# sub.net
KiCad netlist of a schematic drawn in EAGLE
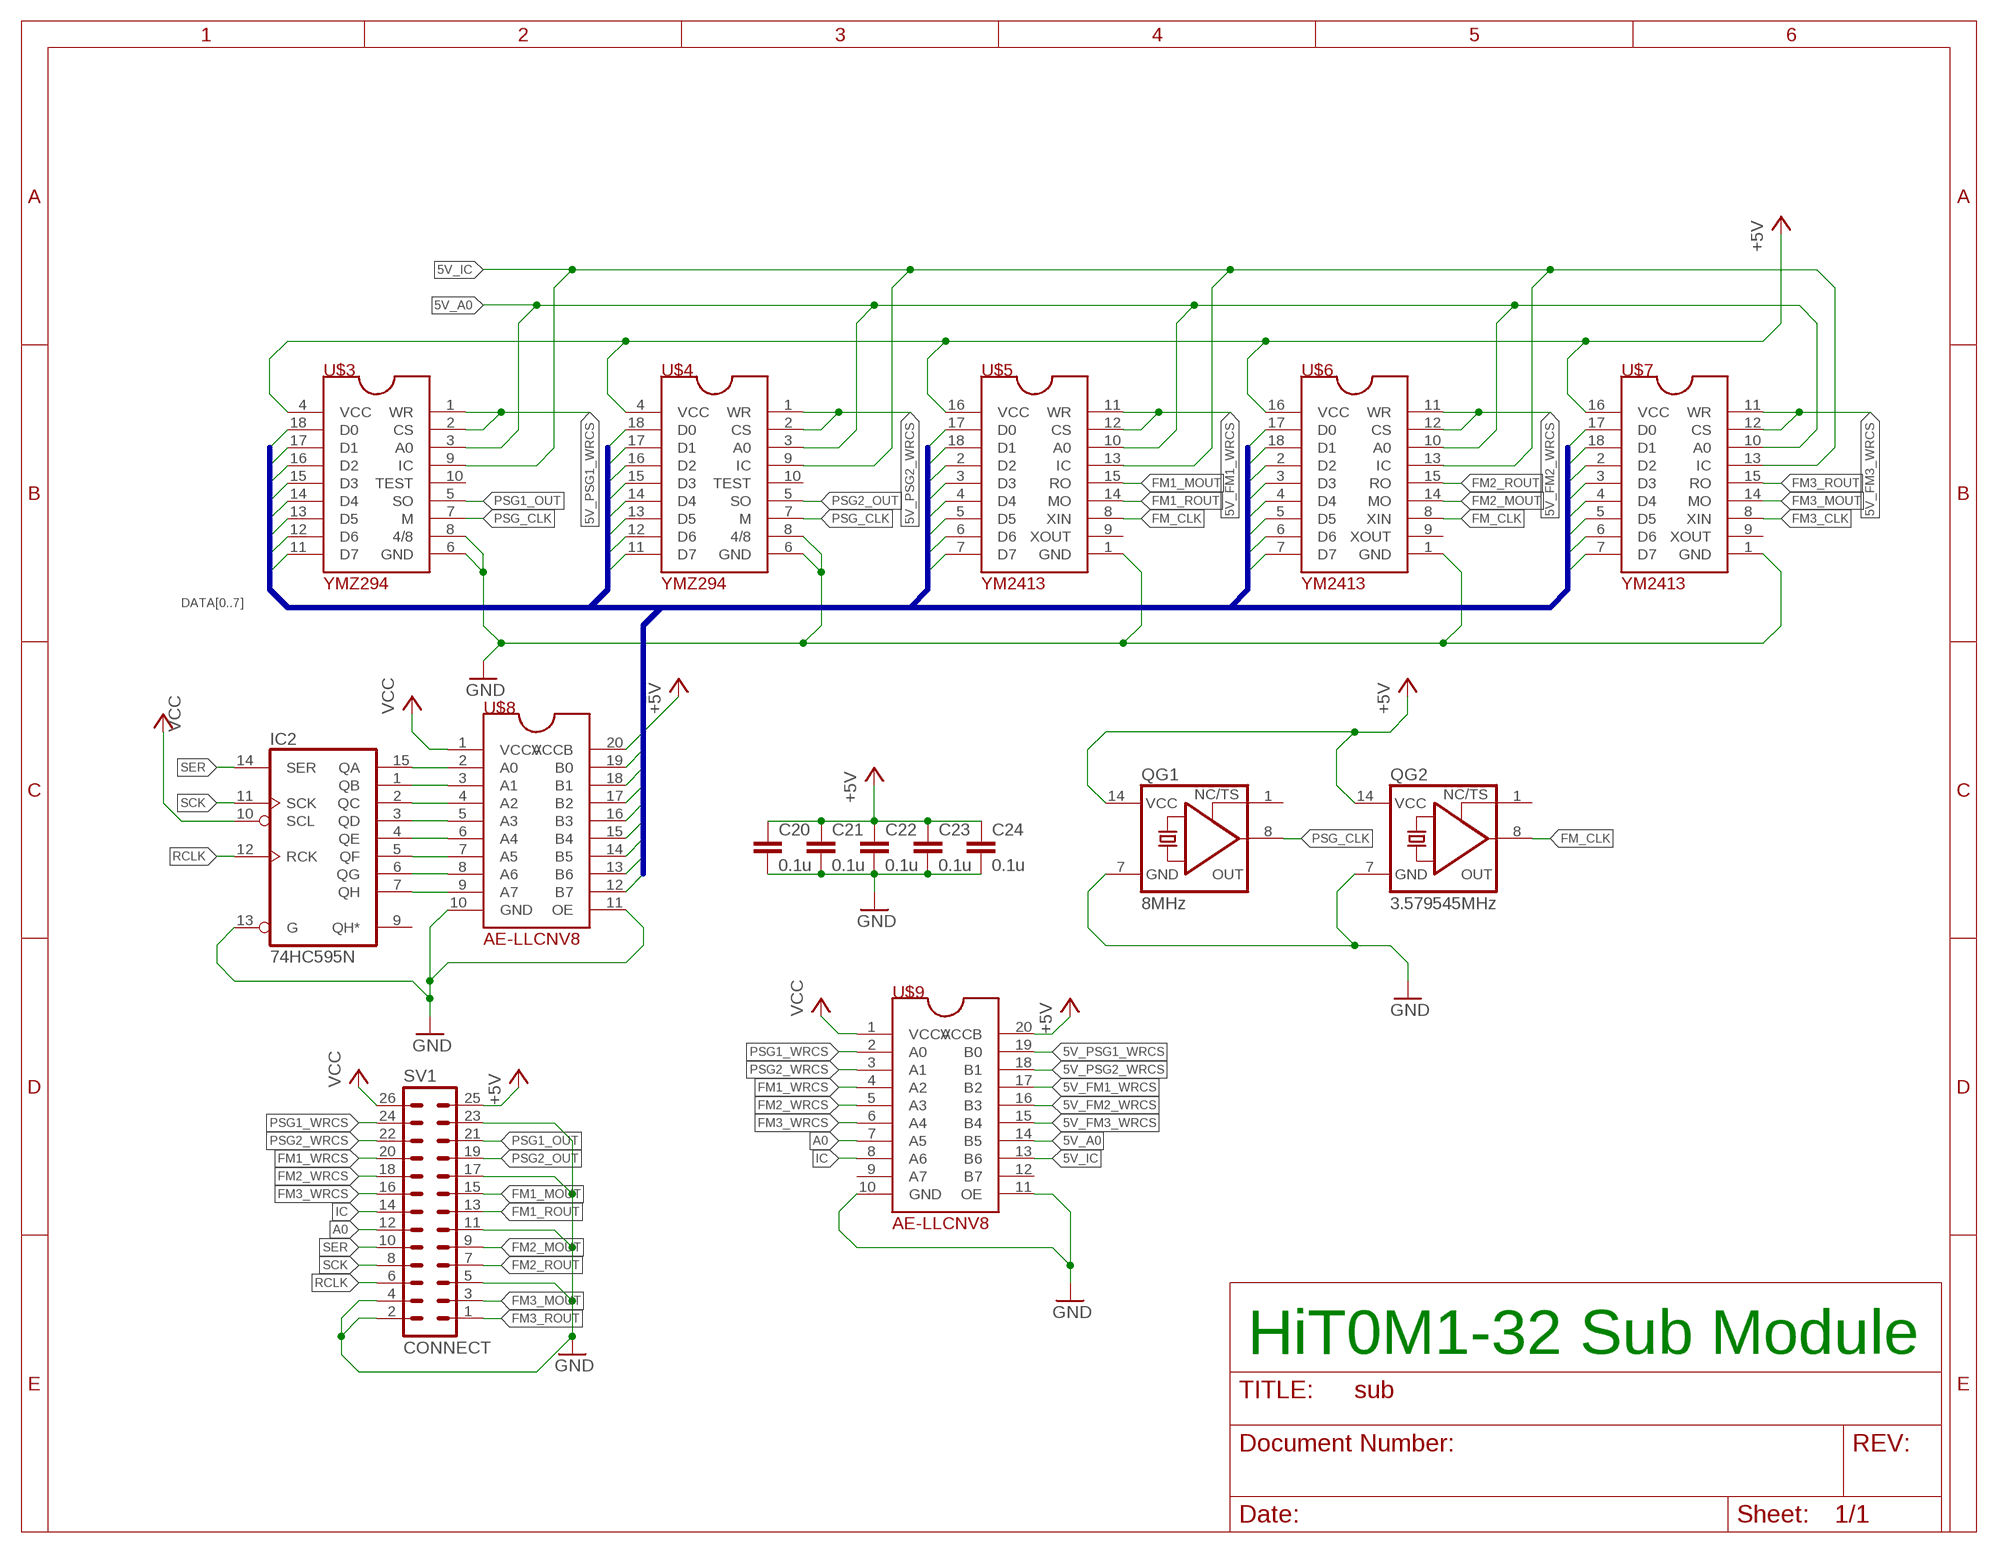
[diagram p0: schematic, sheet 1]

(export (version "E")
  (design (tool "Eeschema 10.0.6"))
  (components
    (comp (ref "C20")
      (value "0.1u")
      (footprint "eagle-import:C025-025X050")
      (libsource (lib "eagle-import") (part "C-EU025-025X050"))
    )
    (comp (ref "C21")
      (value "0.1u")
      (footprint "eagle-import:C025-025X050")
      (libsource (lib "eagle-import") (part "C-EU025-025X050"))
    )
    (comp (ref "C22")
      (value "0.1u")
      (footprint "eagle-import:C025-025X050")
      (libsource (lib "eagle-import") (part "C-EU025-025X050"))
    )
    (comp (ref "C23")
      (value "0.1u")
      (footprint "eagle-import:C025-025X050")
      (libsource (lib "eagle-import") (part "C-EU025-025X050"))
    )
    (comp (ref "C24")
      (value "0.1u")
      (footprint "eagle-import:C025-025X050")
      (libsource (lib "eagle-import") (part "C-EU025-025X050"))
    )
    (comp (ref "IC2")
      (value "74HC595N")
      (footprint "eagle-import:DIL16")
      (libsource (lib "eagle-import") (part "74595NHC"))
    )
    (comp (ref "QG1")
      (value "8MHz")
      (footprint "eagle-import:DIL14S")
      (libsource (lib "eagle-import") (part "XO-14"))
    )
    (comp (ref "QG2")
      (value "3.579545MHz")
      (footprint "eagle-import:DIL14S")
      (libsource (lib "eagle-import") (part "XO-14"))
    )
    (comp (ref "SV1")
      (value "CONNECT")
      (footprint "eagle-import:MA13-2")
      (libsource (lib "eagle-import") (part "MA13-2"))
    )
    (comp (ref "U$3")
      (value "YMZ294")
      (footprint "eagle-import:DIL18")
      (libsource (lib "eagle-import") (part "YMZ294YMZ294"))
    )
    (comp (ref "U$4")
      (value "YMZ294")
      (footprint "eagle-import:DIL18")
      (libsource (lib "eagle-import") (part "YMZ294YMZ294"))
    )
    (comp (ref "U$5")
      (value "YM2413")
      (footprint "eagle-import:DIL18")
      (libsource (lib "eagle-import") (part "YM2413"))
    )
    (comp (ref "U$6")
      (value "YM2413")
      (footprint "eagle-import:DIL18")
      (libsource (lib "eagle-import") (part "YM2413"))
    )
    (comp (ref "U$7")
      (value "YM2413")
      (footprint "eagle-import:DIL18")
      (libsource (lib "eagle-import") (part "YM2413"))
    )
    (comp (ref "U$8")
      (value "AE-LLCNV8")
      (footprint "eagle-import:DIL20")
      (libsource (lib "eagle-import") (part "AE-LLCNV8AE-LLCNV8"))
    )
    (comp (ref "U$9")
      (value "AE-LLCNV8")
      (footprint "eagle-import:DIL20")
      (libsource (lib "eagle-import") (part "AE-LLCNV8AE-LLCNV8"))
    )
  )
  (nets
    (net (code "1") (name "+5V") (class "Default")
      (node (ref "C20") (pin "1") (pinfunction "1_1") (pintype "passive"))
      (node (ref "C21") (pin "1") (pinfunction "1_1") (pintype "passive"))
      (node (ref "C22") (pin "1") (pinfunction "1_1") (pintype "passive"))
      (node (ref "C23") (pin "1") (pinfunction "1_1") (pintype "passive"))
      (node (ref "C24") (pin "1") (pinfunction "1_1") (pintype "passive"))
      (node (ref "QG1") (pin "14") (pinfunction "VCC_14") (pintype "power_in"))
      (node (ref "QG2") (pin "14") (pinfunction "VCC_14") (pintype "power_in"))
      (node (ref "SV1") (pin "25") (pinfunction "25_25") (pintype "passive"))
      (node (ref "U$3") (pin "4") (pinfunction "VCC_4") (pintype "bidirectional"))
      (node (ref "U$4") (pin "4") (pinfunction "VCC_4") (pintype "bidirectional"))
      (node (ref "U$5") (pin "16") (pinfunction "VCC_16") (pintype "bidirectional"))
      (node (ref "U$6") (pin "16") (pinfunction "VCC_16") (pintype "bidirectional"))
      (node (ref "U$7") (pin "16") (pinfunction "VCC_16") (pintype "bidirectional"))
      (node (ref "U$8") (pin "20") (pinfunction "VCCB_20") (pintype "bidirectional"))
      (node (ref "U$9") (pin "20") (pinfunction "VCCB_20") (pintype "bidirectional"))
    )
    (net (code "2") (name "/DATA0") (class "Default")
      (node (ref "U$3") (pin "18") (pinfunction "D0_18") (pintype "bidirectional"))
      (node (ref "U$4") (pin "18") (pinfunction "D0_18") (pintype "bidirectional"))
      (node (ref "U$5") (pin "17") (pinfunction "D0_17") (pintype "bidirectional"))
      (node (ref "U$6") (pin "17") (pinfunction "D0_17") (pintype "bidirectional"))
      (node (ref "U$7") (pin "17") (pinfunction "D0_17") (pintype "bidirectional"))
      (node (ref "U$8") (pin "19") (pinfunction "B0_19") (pintype "bidirectional"))
    )
    (net (code "3") (name "/DATA1") (class "Default")
      (node (ref "U$3") (pin "17") (pinfunction "D1_17") (pintype "bidirectional"))
      (node (ref "U$4") (pin "17") (pinfunction "D1_17") (pintype "bidirectional"))
      (node (ref "U$5") (pin "18") (pinfunction "D1_18") (pintype "bidirectional"))
      (node (ref "U$6") (pin "18") (pinfunction "D1_18") (pintype "bidirectional"))
      (node (ref "U$7") (pin "18") (pinfunction "D1_18") (pintype "bidirectional"))
      (node (ref "U$8") (pin "18") (pinfunction "B1_18") (pintype "bidirectional"))
    )
    (net (code "4") (name "/DATA2") (class "Default")
      (node (ref "U$3") (pin "16") (pinfunction "D2_16") (pintype "bidirectional"))
      (node (ref "U$4") (pin "16") (pinfunction "D2_16") (pintype "bidirectional"))
      (node (ref "U$5") (pin "2") (pinfunction "D2_2") (pintype "bidirectional"))
      (node (ref "U$6") (pin "2") (pinfunction "D2_2") (pintype "bidirectional"))
      (node (ref "U$7") (pin "2") (pinfunction "D2_2") (pintype "bidirectional"))
      (node (ref "U$8") (pin "17") (pinfunction "B2_17") (pintype "bidirectional"))
    )
    (net (code "5") (name "/DATA3") (class "Default")
      (node (ref "U$3") (pin "15") (pinfunction "D3_15") (pintype "bidirectional"))
      (node (ref "U$4") (pin "15") (pinfunction "D3_15") (pintype "bidirectional"))
      (node (ref "U$5") (pin "3") (pinfunction "D3_3") (pintype "bidirectional"))
      (node (ref "U$6") (pin "3") (pinfunction "D3_3") (pintype "bidirectional"))
      (node (ref "U$7") (pin "3") (pinfunction "D3_3") (pintype "bidirectional"))
      (node (ref "U$8") (pin "16") (pinfunction "B3_16") (pintype "bidirectional"))
    )
    (net (code "6") (name "/DATA4") (class "Default")
      (node (ref "U$3") (pin "14") (pinfunction "D4_14") (pintype "bidirectional"))
      (node (ref "U$4") (pin "14") (pinfunction "D4_14") (pintype "bidirectional"))
      (node (ref "U$5") (pin "4") (pinfunction "D4_4") (pintype "bidirectional"))
      (node (ref "U$6") (pin "4") (pinfunction "D4_4") (pintype "bidirectional"))
      (node (ref "U$7") (pin "4") (pinfunction "D4_4") (pintype "bidirectional"))
      (node (ref "U$8") (pin "15") (pinfunction "B4_15") (pintype "bidirectional"))
    )
    (net (code "7") (name "/DATA5") (class "Default")
      (node (ref "U$3") (pin "13") (pinfunction "D5_13") (pintype "bidirectional"))
      (node (ref "U$4") (pin "13") (pinfunction "D5_13") (pintype "bidirectional"))
      (node (ref "U$5") (pin "5") (pinfunction "D5_5") (pintype "bidirectional"))
      (node (ref "U$6") (pin "5") (pinfunction "D5_5") (pintype "bidirectional"))
      (node (ref "U$7") (pin "5") (pinfunction "D5_5") (pintype "bidirectional"))
      (node (ref "U$8") (pin "14") (pinfunction "B5_14") (pintype "bidirectional"))
    )
    (net (code "8") (name "/DATA6") (class "Default")
      (node (ref "U$3") (pin "12") (pinfunction "D6_12") (pintype "bidirectional"))
      (node (ref "U$4") (pin "12") (pinfunction "D6_12") (pintype "bidirectional"))
      (node (ref "U$5") (pin "6") (pinfunction "D6_6") (pintype "bidirectional"))
      (node (ref "U$6") (pin "6") (pinfunction "D6_6") (pintype "bidirectional"))
      (node (ref "U$7") (pin "6") (pinfunction "D6_6") (pintype "bidirectional"))
      (node (ref "U$8") (pin "13") (pinfunction "B6_13") (pintype "bidirectional"))
    )
    (net (code "9") (name "/DATA7") (class "Default")
      (node (ref "U$3") (pin "11") (pinfunction "D7_11") (pintype "bidirectional"))
      (node (ref "U$4") (pin "11") (pinfunction "D7_11") (pintype "bidirectional"))
      (node (ref "U$5") (pin "7") (pinfunction "D7_7") (pintype "bidirectional"))
      (node (ref "U$6") (pin "7") (pinfunction "D7_7") (pintype "bidirectional"))
      (node (ref "U$7") (pin "7") (pinfunction "D7_7") (pintype "bidirectional"))
      (node (ref "U$8") (pin "12") (pinfunction "B7_12") (pintype "bidirectional"))
    )
    (net (code "11") (name "5V_A0") (class "Default")
      (node (ref "U$3") (pin "3") (pinfunction "A0_3") (pintype "bidirectional"))
      (node (ref "U$4") (pin "3") (pinfunction "A0_3") (pintype "bidirectional"))
      (node (ref "U$5") (pin "10") (pinfunction "A0_10") (pintype "bidirectional"))
      (node (ref "U$6") (pin "10") (pinfunction "A0_10") (pintype "bidirectional"))
      (node (ref "U$7") (pin "10") (pinfunction "A0_10") (pintype "bidirectional"))
      (node (ref "U$9") (pin "14") (pinfunction "B5_14") (pintype "bidirectional"))
    )
    (net (code "12") (name "5V_FM1_WRCS") (class "Default")
      (node (ref "U$5") (pin "11") (pinfunction "WR_11") (pintype "bidirectional"))
      (node (ref "U$5") (pin "12") (pinfunction "CS_12") (pintype "bidirectional"))
      (node (ref "U$9") (pin "17") (pinfunction "B2_17") (pintype "bidirectional"))
    )
    (net (code "13") (name "5V_FM2_WRCS") (class "Default")
      (node (ref "U$6") (pin "11") (pinfunction "WR_11") (pintype "bidirectional"))
      (node (ref "U$6") (pin "12") (pinfunction "CS_12") (pintype "bidirectional"))
      (node (ref "U$9") (pin "16") (pinfunction "B3_16") (pintype "bidirectional"))
    )
    (net (code "14") (name "5V_FM3_WRCS") (class "Default")
      (node (ref "U$7") (pin "11") (pinfunction "WR_11") (pintype "bidirectional"))
      (node (ref "U$7") (pin "12") (pinfunction "CS_12") (pintype "bidirectional"))
      (node (ref "U$9") (pin "15") (pinfunction "B4_15") (pintype "bidirectional"))
    )
    (net (code "15") (name "5V_IC") (class "Default")
      (node (ref "U$3") (pin "9") (pinfunction "IC_9") (pintype "bidirectional"))
      (node (ref "U$4") (pin "9") (pinfunction "IC_9") (pintype "bidirectional"))
      (node (ref "U$5") (pin "13") (pinfunction "IC_13") (pintype "bidirectional"))
      (node (ref "U$6") (pin "13") (pinfunction "IC_13") (pintype "bidirectional"))
      (node (ref "U$7") (pin "13") (pinfunction "IC_13") (pintype "bidirectional"))
      (node (ref "U$9") (pin "13") (pinfunction "B6_13") (pintype "bidirectional"))
    )
    (net (code "16") (name "5V_PSG1_WRCS") (class "Default")
      (node (ref "U$3") (pin "1") (pinfunction "WR_1") (pintype "bidirectional"))
      (node (ref "U$3") (pin "2") (pinfunction "CS_2") (pintype "bidirectional"))
      (node (ref "U$9") (pin "19") (pinfunction "B0_19") (pintype "bidirectional"))
    )
    (net (code "17") (name "5V_PSG2_WRCS") (class "Default")
      (node (ref "U$4") (pin "1") (pinfunction "WR_1") (pintype "bidirectional"))
      (node (ref "U$4") (pin "2") (pinfunction "CS_2") (pintype "bidirectional"))
      (node (ref "U$9") (pin "18") (pinfunction "B1_18") (pintype "bidirectional"))
    )
    (net (code "18") (name "A0") (class "Default")
      (node (ref "SV1") (pin "12") (pinfunction "12_12") (pintype "passive"))
      (node (ref "U$9") (pin "7") (pinfunction "A5_7") (pintype "bidirectional"))
    )
    (net (code "19") (name "FM1_MOUT") (class "Default")
      (node (ref "SV1") (pin "15") (pinfunction "15_15") (pintype "passive"))
      (node (ref "U$5") (pin "15") (pinfunction "RO_15") (pintype "bidirectional"))
    )
    (net (code "20") (name "FM1_ROUT") (class "Default")
      (node (ref "SV1") (pin "13") (pinfunction "13_13") (pintype "passive"))
      (node (ref "U$5") (pin "14") (pinfunction "MO_14") (pintype "bidirectional"))
    )
    (net (code "21") (name "FM1_WRCS") (class "Default")
      (node (ref "SV1") (pin "20") (pinfunction "20_20") (pintype "passive"))
      (node (ref "U$9") (pin "4") (pinfunction "A2_4") (pintype "bidirectional"))
    )
    (net (code "22") (name "FM2_MOUT") (class "Default")
      (node (ref "SV1") (pin "9") (pinfunction "9_9") (pintype "passive"))
      (node (ref "U$6") (pin "14") (pinfunction "MO_14") (pintype "bidirectional"))
    )
    (net (code "23") (name "FM2_ROUT") (class "Default")
      (node (ref "SV1") (pin "7") (pinfunction "7_7") (pintype "passive"))
      (node (ref "U$6") (pin "15") (pinfunction "RO_15") (pintype "bidirectional"))
    )
    (net (code "24") (name "FM2_WRCS") (class "Default")
      (node (ref "SV1") (pin "18") (pinfunction "18_18") (pintype "passive"))
      (node (ref "U$9") (pin "5") (pinfunction "A3_5") (pintype "bidirectional"))
    )
    (net (code "25") (name "FM3_CLK") (class "Default")
      (node (ref "U$7") (pin "8") (pinfunction "XIN_8") (pintype "bidirectional"))
    )
    (net (code "26") (name "FM3_MOUT") (class "Default")
      (node (ref "SV1") (pin "3") (pinfunction "3_3") (pintype "passive"))
      (node (ref "U$7") (pin "14") (pinfunction "MO_14") (pintype "bidirectional"))
    )
    (net (code "27") (name "FM3_ROUT") (class "Default")
      (node (ref "SV1") (pin "1") (pinfunction "1_1") (pintype "passive"))
      (node (ref "U$7") (pin "15") (pinfunction "RO_15") (pintype "bidirectional"))
    )
    (net (code "28") (name "FM3_WRCS") (class "Default")
      (node (ref "SV1") (pin "16") (pinfunction "16_16") (pintype "passive"))
      (node (ref "U$9") (pin "6") (pinfunction "A4_6") (pintype "bidirectional"))
    )
    (net (code "29") (name "FM_CLK") (class "Default")
      (node (ref "QG2") (pin "8") (pinfunction "OUT_8") (pintype "output"))
      (node (ref "U$5") (pin "8") (pinfunction "XIN_8") (pintype "bidirectional"))
      (node (ref "U$6") (pin "8") (pinfunction "XIN_8") (pintype "bidirectional"))
    )
    (net (code "30") (name "GND") (class "Default")
      (node (ref "C20") (pin "2") (pinfunction "2_2") (pintype "passive"))
      (node (ref "C21") (pin "2") (pinfunction "2_2") (pintype "passive"))
      (node (ref "C22") (pin "2") (pinfunction "2_2") (pintype "passive"))
      (node (ref "C23") (pin "2") (pinfunction "2_2") (pintype "passive"))
      (node (ref "C24") (pin "2") (pinfunction "2_2") (pintype "passive"))
      (node (ref "IC2") (pin "13") (pinfunction "G_13") (pintype "input"))
      (node (ref "QG1") (pin "7") (pinfunction "GND_7") (pintype "power_in"))
      (node (ref "QG2") (pin "7") (pinfunction "GND_7") (pintype "power_in"))
      (node (ref "SV1") (pin "11") (pinfunction "11_11") (pintype "passive"))
      (node (ref "SV1") (pin "17") (pinfunction "17_17") (pintype "passive"))
      (node (ref "SV1") (pin "2") (pinfunction "2_2") (pintype "passive"))
      (node (ref "SV1") (pin "23") (pinfunction "23_23") (pintype "passive"))
      (node (ref "SV1") (pin "4") (pinfunction "4_4") (pintype "passive"))
      (node (ref "SV1") (pin "5") (pinfunction "5_5") (pintype "passive"))
      (node (ref "U$3") (pin "6") (pinfunction "GND_6") (pintype "bidirectional"))
      (node (ref "U$3") (pin "8") (pinfunction "4/8_8") (pintype "bidirectional"))
      (node (ref "U$4") (pin "6") (pinfunction "GND_6") (pintype "bidirectional"))
      (node (ref "U$4") (pin "8") (pinfunction "4/8_8") (pintype "bidirectional"))
      (node (ref "U$5") (pin "1") (pinfunction "GND_1") (pintype "bidirectional"))
      (node (ref "U$6") (pin "1") (pinfunction "GND_1") (pintype "bidirectional"))
      (node (ref "U$7") (pin "1") (pinfunction "GND_1") (pintype "bidirectional"))
      (node (ref "U$8") (pin "10") (pinfunction "GND_10") (pintype "bidirectional"))
      (node (ref "U$8") (pin "11") (pinfunction "OE_11") (pintype "bidirectional"))
      (node (ref "U$9") (pin "10") (pinfunction "GND_10") (pintype "bidirectional"))
      (node (ref "U$9") (pin "11") (pinfunction "OE_11") (pintype "bidirectional"))
    )
    (net (code "31") (name "IC") (class "Default")
      (node (ref "SV1") (pin "14") (pinfunction "14_14") (pintype "passive"))
      (node (ref "U$9") (pin "8") (pinfunction "A6_8") (pintype "bidirectional"))
    )
    (net (code "32") (name "Net-(IC2A-QA)") (class "Default")
      (node (ref "IC2") (pin "15") (pinfunction "QA_15") (pintype "tri_state"))
      (node (ref "U$8") (pin "2") (pinfunction "A0_2") (pintype "bidirectional"))
    )
    (net (code "33") (name "Net-(IC2A-QB)") (class "Default")
      (node (ref "IC2") (pin "1") (pinfunction "QB_1") (pintype "tri_state"))
      (node (ref "U$8") (pin "3") (pinfunction "A1_3") (pintype "bidirectional"))
    )
    (net (code "34") (name "Net-(IC2A-QC)") (class "Default")
      (node (ref "IC2") (pin "2") (pinfunction "QC_2") (pintype "tri_state"))
      (node (ref "U$8") (pin "4") (pinfunction "A2_4") (pintype "bidirectional"))
    )
    (net (code "35") (name "Net-(IC2A-QD)") (class "Default")
      (node (ref "IC2") (pin "3") (pinfunction "QD_3") (pintype "tri_state"))
      (node (ref "U$8") (pin "5") (pinfunction "A3_5") (pintype "bidirectional"))
    )
    (net (code "36") (name "Net-(IC2A-QE)") (class "Default")
      (node (ref "IC2") (pin "4") (pinfunction "QE_4") (pintype "tri_state"))
      (node (ref "U$8") (pin "6") (pinfunction "A4_6") (pintype "bidirectional"))
    )
    (net (code "37") (name "Net-(IC2A-QF)") (class "Default")
      (node (ref "IC2") (pin "5") (pinfunction "QF_5") (pintype "tri_state"))
      (node (ref "U$8") (pin "7") (pinfunction "A5_7") (pintype "bidirectional"))
    )
    (net (code "38") (name "Net-(IC2A-QG)") (class "Default")
      (node (ref "IC2") (pin "6") (pinfunction "QG_6") (pintype "tri_state"))
      (node (ref "U$8") (pin "8") (pinfunction "A6_8") (pintype "bidirectional"))
    )
    (net (code "39") (name "Net-(IC2A-QH)") (class "Default")
      (node (ref "IC2") (pin "7") (pinfunction "QH_7") (pintype "tri_state"))
      (node (ref "U$8") (pin "9") (pinfunction "A7_9") (pintype "bidirectional"))
    )
    (net (code "40") (name "PSG1_OUT") (class "Default")
      (node (ref "SV1") (pin "21") (pinfunction "21_21") (pintype "passive"))
      (node (ref "U$3") (pin "5") (pinfunction "SO_5") (pintype "bidirectional"))
    )
    (net (code "41") (name "PSG1_WRCS") (class "Default")
      (node (ref "SV1") (pin "24") (pinfunction "24_24") (pintype "passive"))
      (node (ref "U$9") (pin "2") (pinfunction "A0_2") (pintype "bidirectional"))
    )
    (net (code "42") (name "PSG2_OUT") (class "Default")
      (node (ref "SV1") (pin "19") (pinfunction "19_19") (pintype "passive"))
      (node (ref "U$4") (pin "5") (pinfunction "SO_5") (pintype "bidirectional"))
    )
    (net (code "43") (name "PSG2_WRCS") (class "Default")
      (node (ref "SV1") (pin "22") (pinfunction "22_22") (pintype "passive"))
      (node (ref "U$9") (pin "3") (pinfunction "A1_3") (pintype "bidirectional"))
    )
    (net (code "44") (name "PSG_CLK") (class "Default")
      (node (ref "QG1") (pin "8") (pinfunction "OUT_8") (pintype "output"))
      (node (ref "U$3") (pin "7") (pinfunction "M_7") (pintype "bidirectional"))
      (node (ref "U$4") (pin "7") (pinfunction "M_7") (pintype "bidirectional"))
    )
    (net (code "45") (name "RCLK") (class "Default")
      (node (ref "IC2") (pin "12") (pinfunction "RCK_12") (pintype "input"))
      (node (ref "SV1") (pin "6") (pinfunction "6_6") (pintype "passive"))
    )
    (net (code "46") (name "SCK") (class "Default")
      (node (ref "IC2") (pin "11") (pinfunction "SCK_11") (pintype "input"))
      (node (ref "SV1") (pin "8") (pinfunction "8_8") (pintype "passive"))
    )
    (net (code "47") (name "SER") (class "Default")
      (node (ref "IC2") (pin "14") (pinfunction "SER_14") (pintype "input"))
      (node (ref "SV1") (pin "10") (pinfunction "10_10") (pintype "passive"))
    )
    (net (code "48") (name "VCC") (class "Default")
      (node (ref "IC2") (pin "10") (pinfunction "SCL_10") (pintype "input"))
      (node (ref "SV1") (pin "26") (pinfunction "26_26") (pintype "passive"))
      (node (ref "U$8") (pin "1") (pinfunction "VCCA_1") (pintype "bidirectional"))
      (node (ref "U$9") (pin "1") (pinfunction "VCCA_1") (pintype "bidirectional"))
    )
    (net (code "49") (name "unconnected-(IC2A-QH*-Pad9)") (class "Default")
      (node (ref "IC2") (pin "9") (pinfunction "QH*_9") (pintype "tri_state"))
    )
    (net (code "50") (name "unconnected-(QG1-TS-Pad1)") (class "Default")
      (node (ref "QG1") (pin "1") (pinfunction "TS_1") (pintype "passive"))
    )
    (net (code "51") (name "unconnected-(QG2-TS-Pad1)") (class "Default")
      (node (ref "QG2") (pin "1") (pinfunction "TS_1") (pintype "passive"))
    )
    (net (code "52") (name "unconnected-(U$3-TEST-Pad10)") (class "Default")
      (node (ref "U$3") (pin "10") (pinfunction "TEST_10") (pintype "bidirectional"))
    )
    (net (code "53") (name "unconnected-(U$4-TEST-Pad10)") (class "Default")
      (node (ref "U$4") (pin "10") (pinfunction "TEST_10") (pintype "bidirectional"))
    )
    (net (code "54") (name "unconnected-(U$5-XOUT-Pad9)") (class "Default")
      (node (ref "U$5") (pin "9") (pinfunction "XOUT_9") (pintype "bidirectional"))
    )
    (net (code "55") (name "unconnected-(U$6-XOUT-Pad9)") (class "Default")
      (node (ref "U$6") (pin "9") (pinfunction "XOUT_9") (pintype "bidirectional"))
    )
    (net (code "56") (name "unconnected-(U$7-XOUT-Pad9)") (class "Default")
      (node (ref "U$7") (pin "9") (pinfunction "XOUT_9") (pintype "bidirectional"))
    )
    (net (code "57") (name "unconnected-(U$9-A7-Pad9)") (class "Default")
      (node (ref "U$9") (pin "9") (pinfunction "A7_9") (pintype "bidirectional"))
    )
    (net (code "58") (name "unconnected-(U$9-B7-Pad12)") (class "Default")
      (node (ref "U$9") (pin "12") (pinfunction "B7_12") (pintype "bidirectional"))
    )
  )
)
